# Driver2.net
KiCad netlist of a schematic drawn in Altium Designer
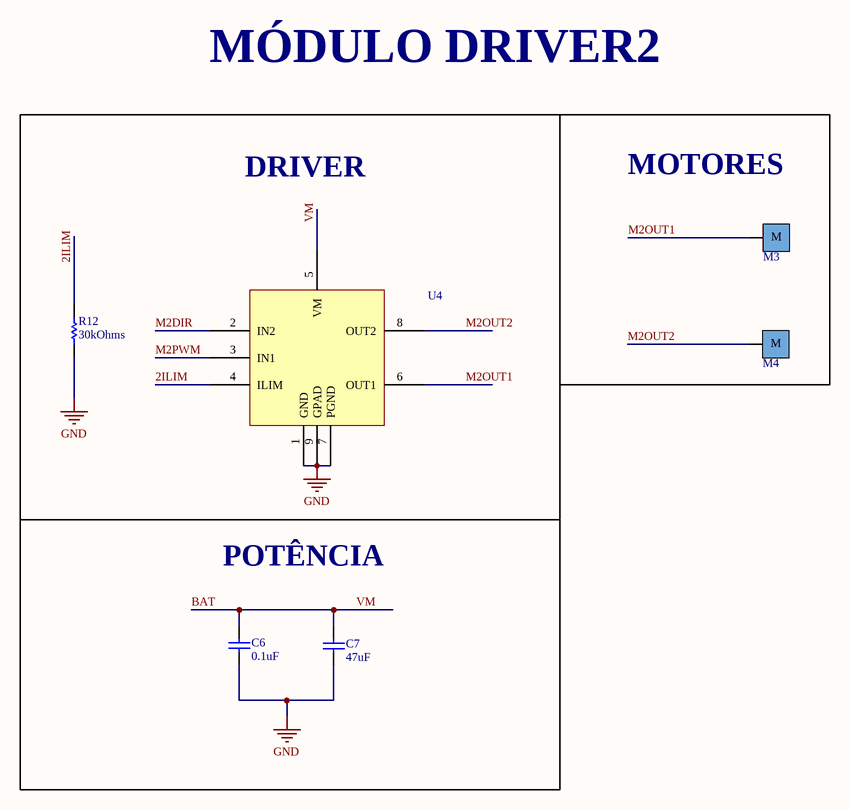
[diagram p0: Driver2.SchDoc]

(export (version "E")
  (design (tool "Eeschema 10.0.6"))
  (components
    (comp (ref "C6")
      (value "0.1uF")
      (footprint "C0805")
      (description "CAP CER 100nF 25V X7R 0805")
      (fields
        (field (name "MANUFACTURER") "Kemet")
        (field (name "PART NUMBER") "C0805C104M3RACTU")
        (field (name "LIBRARY CONTROL - PERSON THAT CHECKED FOOTPRINT") "Cage")
        (field (name "LIBRARY CONTROL - PERSON THAT CHECKED SCHEMATIC") "Cage")
        (field (name "LIBRARY CONTROL - PERSON THAT DID THE LAST UPDATE FOOTPRINT") "Cage")
        (field (name "LIBRARY CONTROL - PERSON THAT DID THE LAST UPDATE SCHEMATIC") "Cage")
      )
      (libsource (lib "Uai!Tecas") (part "C0805C104M3RACTU"))
    )
    (comp (ref "C7")
      (value "47uF")
      (footprint "C1210")
      (description "CAP CER 47uF 16V X6S 1210")
      (fields
        (field (name "MANUFACTURER") "Murata")
        (field (name "PART NUMBER") "GRM32EC81C476KE15K")
        (field (name "LIBRARY CONTROL - PERSON THAT CHECKED FOOTPRINT") "Cage")
        (field (name "LIBRARY CONTROL - PERSON THAT CHECKED SCHEMATIC") "Cage")
        (field (name "LIBRARY CONTROL - PERSON THAT DID THE LAST UPDATE FOOTPRINT") "Prisma")
        (field (name "LIBRARY CONTROL - PERSON THAT DID THE LAST UPDATE SCHEMATIC") "Prisma")
      )
      (libsource (lib "Capacitor") (part "GRM32EC81C476KE15K"))
    )
    (comp (ref "M3")
      (value "Motor Pad")
      (footprint "PAD_MOTOR_MINI")
      (description "MOTOR PAD MINI SUMÔ")
      (libsource (lib "Uai!Tecas") (part "Motor Pad Mini Sumô"))
    )
    (comp (ref "M4")
      (value "Motor Pad")
      (footprint "PAD_MOTOR_MINI")
      (description "MOTOR PAD MINI SUMÔ")
      (libsource (lib "Uai!Tecas") (part "Motor Pad Mini Sumô"))
    )
    (comp (ref "R12")
      (value "30kOhms")
      (footprint "RESC1608X55N")
      (description "RES SMD 30 kOHMS 1% 1/10W 0603")
      (fields
        (field (name "MANUFACTURER") "YAGEO")
        (field (name "PART NUMBER") "RC0603FR-0730KL")
        (field (name "LIBRARY CONTROL - PERSON THAT CHECKED FOOTPRINT") "Guilherme")
        (field (name "LIBRARY CONTROL - PERSON THAT CHECKED SCHEMATIC") "Guilherme")
        (field (name "LIBRARY CONTROL - PERSON THAT DID THE LAST UPDATE FOOTPRINT") "Guilherme")
        (field (name "LIBRARY CONTROL - PERSON THAT DID THE LAST UPDATE SCHEMATIC") "Guilherme")
      )
      (libsource (lib "Uai!Tecas") (part "RC0603FR-0730KL"))
    )
    (comp (ref "U4")
      (value "DRV8871DDA")
      (footprint "SO-PowerPad-8(8_pins)")
      (description "IC MTR DRV (6.5V ~ 45V) (3.5 A) SO-PowerPad-8")
      (fields
        (field (name "MANUFACTURER") "Texas Instruments")
        (field (name "LIBRARY CONTROL - PERSON THAT CHECKED SCHEMATIC") "Stéfany (Ster)")
        (field (name "LIBRARY CONTROL - PERSON THAT CHECKED FOOTPRINT") "Stéfany (Ster)")
        (field (name "LIBRARY CONTROL - PERSON THAT DID THE LAST UPDATE SCHEMATIC") "Stéfany (Ster)")
        (field (name "LIBRARY CONTROL - PERSON THAT DID THE LAST UPDATE FOOTPRINT") "Maria Laura")
      )
      (libsource (lib "Uai!Tecas") (part "DRV8871DDA"))
    )
  )
  (nets
    (net (code "1") (name "/2ILIM") (class "Default")
      (node (ref "R12") (pin "1") (pinfunction "1_1") (pintype "passive"))
      (node (ref "U4") (pin "4") (pinfunction "ILIM_4") (pintype "passive"))
    )
    (net (code "2") (name "/BAT") (class "Default")
      (node (ref "C6") (pin "2") (pinfunction "2_2") (pintype "passive"))
      (node (ref "C7") (pin "2") (pinfunction "2_2") (pintype "passive"))
      (node (ref "U4") (pin "5") (pinfunction "VM_5") (pintype "passive"))
    )
    (net (code "3") (name "/M2DIR") (class "Default")
      (node (ref "U4") (pin "2") (pinfunction "IN2_2") (pintype "passive"))
    )
    (net (code "4") (name "/M2OUT1") (class "Default")
      (node (ref "M3") (pin "M") (pinfunction "M_M") (pintype "passive"))
      (node (ref "U4") (pin "6") (pinfunction "OUT1_6") (pintype "passive"))
    )
    (net (code "5") (name "/M2OUT2") (class "Default")
      (node (ref "M4") (pin "M") (pinfunction "M_M") (pintype "passive"))
      (node (ref "U4") (pin "8") (pinfunction "OUT2_8") (pintype "passive"))
    )
    (net (code "6") (name "/M2PWM") (class "Default")
      (node (ref "U4") (pin "3") (pinfunction "IN1_3") (pintype "passive"))
    )
    (net (code "7") (name "GND") (class "Default")
      (node (ref "C6") (pin "1") (pinfunction "1_1") (pintype "passive"))
      (node (ref "C7") (pin "1") (pinfunction "1_1") (pintype "passive"))
      (node (ref "R12") (pin "2") (pinfunction "2_2") (pintype "passive"))
      (node (ref "U4") (pin "1") (pinfunction "GND_1") (pintype "passive"))
      (node (ref "U4") (pin "7") (pinfunction "PGND_7") (pintype "passive"))
      (node (ref "U4") (pin "9") (pinfunction "GPAD_9") (pintype "passive"))
    )
  )
)
